# DRV8313_Main.net
KiCad netlist of a schematic drawn in Altium Designer
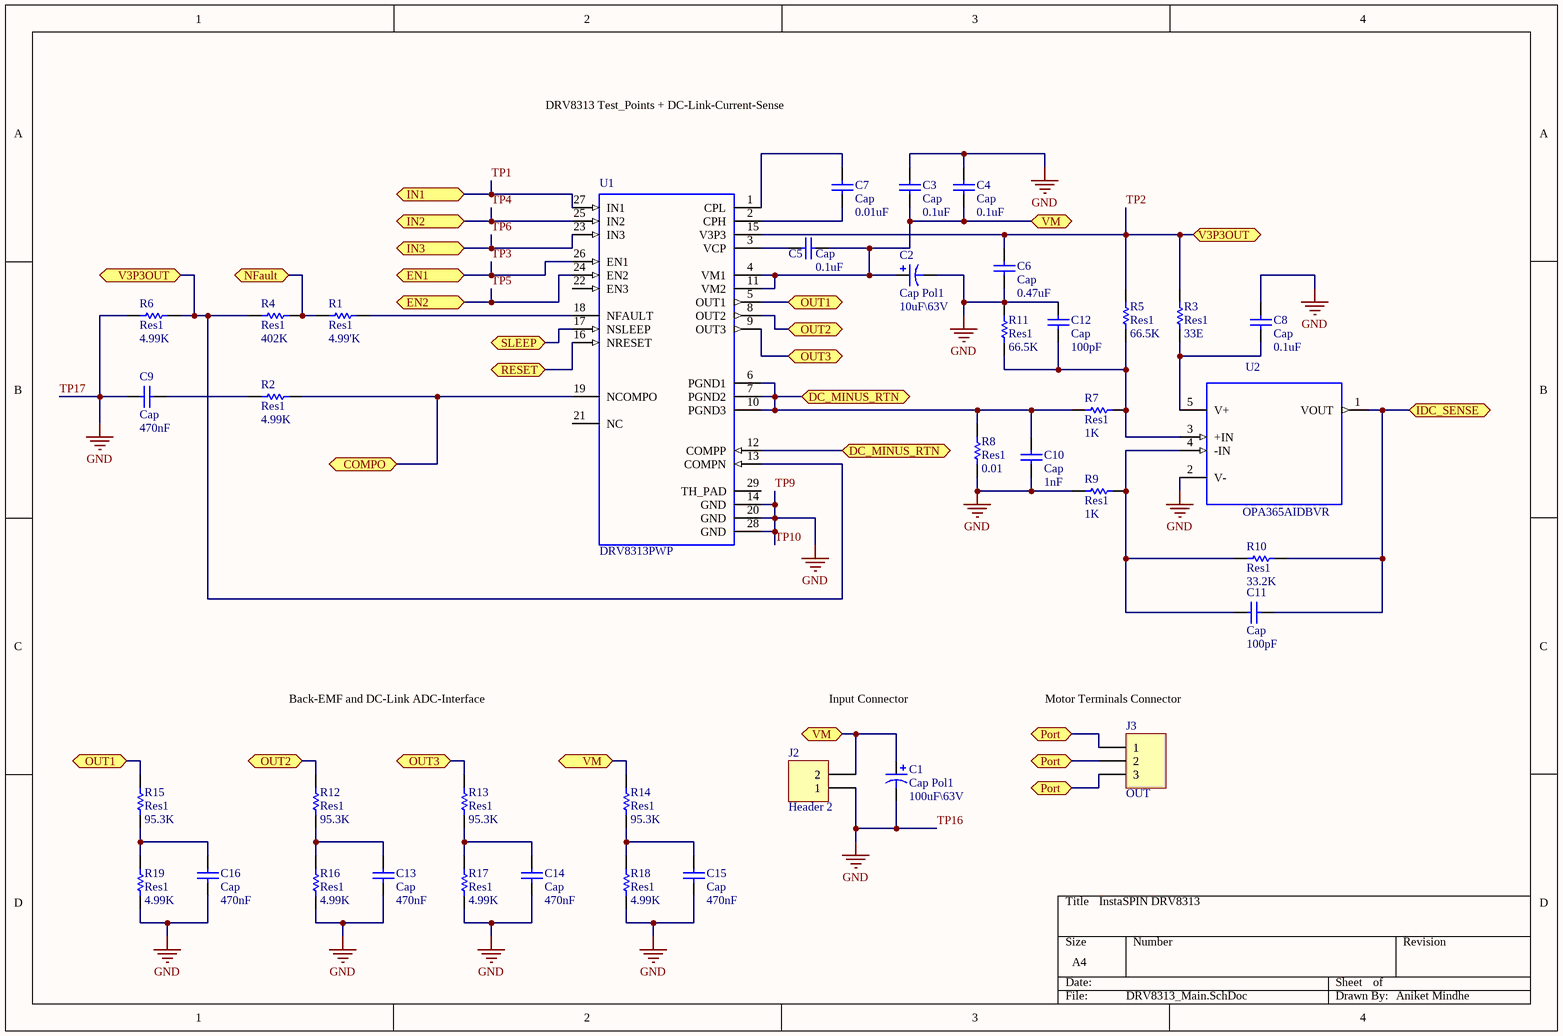
[diagram p0: DRV8313_Main.SchDoc]

(export (version "E")
  (design (tool "Eeschema 10.0.6"))
  (components
    (comp (ref "C1")
      (value "Cap Pol1")
      (footprint "RB7.6-15")
      (description "Polarized Capacitor (Radial)")
      (fields (field (name "ALTIUM_VALUE") "100u~{F}63V") (field (name "PUBLISHER") "Altium Limited"))
      (libsource (lib "Miscellaneous Devices") (part "Cap Pol1"))
    )
    (comp (ref "C2")
      (value "Cap Pol1")
      (footprint "RB7.6-15")
      (description "Polarized Capacitor (Radial)")
      (fields (field (name "ALTIUM_VALUE") "10u~{F}63V") (field (name "PUBLISHER") "Altium Limited"))
      (libsource (lib "Miscellaneous Devices") (part "Cap Pol1"))
    )
    (comp (ref "C3")
      (value "Cap")
      (footprint "RAD-0.3")
      (description "Capacitor")
      (fields (field (name "ALTIUM_VALUE") "0.1uF") (field (name "PUBLISHER") "Altium Limited"))
      (libsource (lib "Miscellaneous Devices") (part "Cap"))
    )
    (comp (ref "C4")
      (value "Cap")
      (footprint "RAD-0.3")
      (description "Capacitor")
      (fields (field (name "ALTIUM_VALUE") "0.1uF") (field (name "PUBLISHER") "Altium Limited"))
      (libsource (lib "Miscellaneous Devices") (part "Cap"))
    )
    (comp (ref "C5")
      (value "Cap")
      (footprint "RAD-0.3")
      (description "Capacitor")
      (fields (field (name "ALTIUM_VALUE") "0.1uF") (field (name "PUBLISHER") "Altium Limited"))
      (libsource (lib "Miscellaneous Devices") (part "Cap"))
    )
    (comp (ref "C6")
      (value "Cap")
      (footprint "RAD-0.3")
      (description "Capacitor")
      (fields (field (name "ALTIUM_VALUE") "0.47uF") (field (name "PUBLISHER") "Altium Limited"))
      (libsource (lib "Miscellaneous Devices") (part "Cap"))
    )
    (comp (ref "C7")
      (value "Cap")
      (footprint "RAD-0.3")
      (description "Capacitor")
      (fields (field (name "ALTIUM_VALUE") "0.01uF") (field (name "PUBLISHER") "Altium Limited"))
      (libsource (lib "Miscellaneous Devices") (part "Cap"))
    )
    (comp (ref "C8")
      (value "Cap")
      (footprint "RAD-0.3")
      (description "Capacitor")
      (fields (field (name "ALTIUM_VALUE") "0.1uF") (field (name "PUBLISHER") "Altium Limited"))
      (libsource (lib "Miscellaneous Devices") (part "Cap"))
    )
    (comp (ref "C9")
      (value "Cap")
      (footprint "RAD-0.3")
      (description "Capacitor")
      (fields (field (name "ALTIUM_VALUE") "470nF") (field (name "PUBLISHER") "Altium Limited"))
      (libsource (lib "Miscellaneous Devices") (part "Cap"))
    )
    (comp (ref "C10")
      (value "Cap")
      (footprint "RAD-0.3")
      (description "Capacitor")
      (fields (field (name "ALTIUM_VALUE") "1nF") (field (name "PUBLISHER") "Altium Limited"))
      (libsource (lib "Miscellaneous Devices") (part "Cap"))
    )
    (comp (ref "C11")
      (value "Cap")
      (footprint "RAD-0.3")
      (description "Capacitor")
      (fields (field (name "ALTIUM_VALUE") "100pF") (field (name "PUBLISHER") "Altium Limited"))
      (libsource (lib "Miscellaneous Devices") (part "Cap"))
    )
    (comp (ref "C12")
      (value "Cap")
      (footprint "RAD-0.3")
      (description "Capacitor")
      (fields (field (name "ALTIUM_VALUE") "100pF") (field (name "PUBLISHER") "Altium Limited"))
      (libsource (lib "Miscellaneous Devices") (part "Cap"))
    )
    (comp (ref "C13")
      (value "Cap")
      (footprint "RAD-0.3")
      (description "Capacitor")
      (fields (field (name "ALTIUM_VALUE") "470nF") (field (name "PUBLISHER") "Altium Limited"))
      (libsource (lib "Miscellaneous Devices") (part "Cap"))
    )
    (comp (ref "C14")
      (value "Cap")
      (footprint "RAD-0.3")
      (description "Capacitor")
      (fields (field (name "ALTIUM_VALUE") "470nF") (field (name "PUBLISHER") "Altium Limited"))
      (libsource (lib "Miscellaneous Devices") (part "Cap"))
    )
    (comp (ref "C15")
      (value "Cap")
      (footprint "RAD-0.3")
      (description "Capacitor")
      (fields (field (name "ALTIUM_VALUE") "470nF") (field (name "PUBLISHER") "Altium Limited"))
      (libsource (lib "Miscellaneous Devices") (part "Cap"))
    )
    (comp (ref "C16")
      (value "Cap")
      (footprint "RAD-0.3")
      (description "Capacitor")
      (fields (field (name "ALTIUM_VALUE") "470nF") (field (name "PUBLISHER") "Altium Limited"))
      (libsource (lib "Miscellaneous Devices") (part "Cap"))
    )
    (comp (ref "J2")
      (value "Header 2")
      (footprint "HDR1X2")
      (description "Header, 2-Pin")
      (fields (field (name "PUBLISHER") "Altium Limited"))
      (libsource (lib "Miscellaneous Connectors") (part "Header 2"))
    )
    (comp (ref "J3")
      (value "OUT")
      (footprint "HDR1X3")
      (description "Header, 3-Pin")
      (fields (field (name "PUBLISHER") "Altium Limited"))
      (libsource (lib "Miscellaneous Connectors") (part "Header 3"))
    )
    (comp (ref "R1")
      (value "Res1")
      (footprint "AXIAL-0.3")
      (description "Resistor")
      (fields (field (name "ALTIUM_VALUE") "4.99'K") (field (name "PUBLISHER") "Altium Limited"))
      (libsource (lib "Miscellaneous Devices") (part "Res1"))
    )
    (comp (ref "R2")
      (value "Res1")
      (footprint "AXIAL-0.3")
      (description "Resistor")
      (fields (field (name "ALTIUM_VALUE") "4.99K") (field (name "PUBLISHER") "Altium Limited"))
      (libsource (lib "Miscellaneous Devices") (part "Res1"))
    )
    (comp (ref "R3")
      (value "Res1")
      (footprint "AXIAL-0.3")
      (description "Resistor")
      (fields (field (name "ALTIUM_VALUE") "33E") (field (name "PUBLISHER") "Altium Limited"))
      (libsource (lib "Miscellaneous Devices") (part "Res1"))
    )
    (comp (ref "R4")
      (value "Res1")
      (footprint "AXIAL-0.3")
      (description "Resistor")
      (fields (field (name "ALTIUM_VALUE") "402K") (field (name "PUBLISHER") "Altium Limited"))
      (libsource (lib "Miscellaneous Devices") (part "Res1"))
    )
    (comp (ref "R5")
      (value "Res1")
      (footprint "AXIAL-0.3")
      (description "Resistor")
      (fields (field (name "ALTIUM_VALUE") "66.5K") (field (name "PUBLISHER") "Altium Limited"))
      (libsource (lib "Miscellaneous Devices") (part "Res1"))
    )
    (comp (ref "R6")
      (value "Res1")
      (footprint "AXIAL-0.3")
      (description "Resistor")
      (fields (field (name "ALTIUM_VALUE") "4.99K") (field (name "PUBLISHER") "Altium Limited"))
      (libsource (lib "Miscellaneous Devices") (part "Res1"))
    )
    (comp (ref "R7")
      (value "Res1")
      (footprint "AXIAL-0.3")
      (description "Resistor")
      (fields (field (name "ALTIUM_VALUE") "1K") (field (name "PUBLISHER") "Altium Limited"))
      (libsource (lib "Miscellaneous Devices") (part "Res1"))
    )
    (comp (ref "R8")
      (value "Res1")
      (footprint "AXIAL-0.3")
      (description "Resistor")
      (fields (field (name "ALTIUM_VALUE") "0.01") (field (name "PUBLISHER") "Altium Limited"))
      (libsource (lib "Miscellaneous Devices") (part "Res1"))
    )
    (comp (ref "R9")
      (value "Res1")
      (footprint "AXIAL-0.3")
      (description "Resistor")
      (fields (field (name "ALTIUM_VALUE") "1K") (field (name "PUBLISHER") "Altium Limited"))
      (libsource (lib "Miscellaneous Devices") (part "Res1"))
    )
    (comp (ref "R10")
      (value "Res1")
      (footprint "AXIAL-0.3")
      (description "Resistor")
      (fields (field (name "ALTIUM_VALUE") "33.2K") (field (name "PUBLISHER") "Altium Limited"))
      (libsource (lib "Miscellaneous Devices") (part "Res1"))
    )
    (comp (ref "R11")
      (value "Res1")
      (footprint "AXIAL-0.3")
      (description "Resistor")
      (fields (field (name "ALTIUM_VALUE") "66.5K") (field (name "PUBLISHER") "Altium Limited"))
      (libsource (lib "Miscellaneous Devices") (part "Res1"))
    )
    (comp (ref "R12")
      (value "Res1")
      (footprint "AXIAL-0.3")
      (description "Resistor")
      (fields (field (name "ALTIUM_VALUE") "95.3K") (field (name "PUBLISHER") "Altium Limited"))
      (libsource (lib "Miscellaneous Devices") (part "Res1"))
    )
    (comp (ref "R13")
      (value "Res1")
      (footprint "AXIAL-0.3")
      (description "Resistor")
      (fields (field (name "ALTIUM_VALUE") "95.3K") (field (name "PUBLISHER") "Altium Limited"))
      (libsource (lib "Miscellaneous Devices") (part "Res1"))
    )
    (comp (ref "R14")
      (value "Res1")
      (footprint "AXIAL-0.3")
      (description "Resistor")
      (fields (field (name "ALTIUM_VALUE") "95.3K") (field (name "PUBLISHER") "Altium Limited"))
      (libsource (lib "Miscellaneous Devices") (part "Res1"))
    )
    (comp (ref "R15")
      (value "Res1")
      (footprint "AXIAL-0.3")
      (description "Resistor")
      (fields (field (name "ALTIUM_VALUE") "95.3K") (field (name "PUBLISHER") "Altium Limited"))
      (libsource (lib "Miscellaneous Devices") (part "Res1"))
    )
    (comp (ref "R16")
      (value "Res1")
      (footprint "AXIAL-0.3")
      (description "Resistor")
      (fields (field (name "ALTIUM_VALUE") "4.99K") (field (name "PUBLISHER") "Altium Limited"))
      (libsource (lib "Miscellaneous Devices") (part "Res1"))
    )
    (comp (ref "R17")
      (value "Res1")
      (footprint "AXIAL-0.3")
      (description "Resistor")
      (fields (field (name "ALTIUM_VALUE") "4.99K") (field (name "PUBLISHER") "Altium Limited"))
      (libsource (lib "Miscellaneous Devices") (part "Res1"))
    )
    (comp (ref "R18")
      (value "Res1")
      (footprint "AXIAL-0.3")
      (description "Resistor")
      (fields (field (name "ALTIUM_VALUE") "4.99K") (field (name "PUBLISHER") "Altium Limited"))
      (libsource (lib "Miscellaneous Devices") (part "Res1"))
    )
    (comp (ref "R19")
      (value "Res1")
      (footprint "AXIAL-0.3")
      (description "Resistor")
      (fields (field (name "ALTIUM_VALUE") "4.99K") (field (name "PUBLISHER") "Altium Limited"))
      (libsource (lib "Miscellaneous Devices") (part "Res1"))
    )
    (comp (ref "U1")
      (value "DRV8313PWP")
      (footprint "SOP28P65_970X640X120L60X24T483X275N")
      (description "2.5A Three Phase Brushless DC Motor Driver _PWM Ctrl_ 28-HTSSOP -40 to 85")
      (fields (field (name "MF") "Texas Instruments"))
      (libsource (lib "DRV8313PWP") (part "DRV8313PWP"))
    )
    (comp (ref "U2")
      (value "OPA365AIDBVR")
      (footprint "SOT95P280X145-5N")
      (description "2.2V, 50MHz, Low-Noise, Single-Supply Rail-to-Rail Operational Amplifier 5-SOT-23 -40 to 125")
      (fields (field (name "MF") "Texas Instruments"))
      (libsource (lib "OPA365AIDBVR") (part "OPA365AIDBVR"))
    )
  )
  (nets
    (net (code "1") (name "/COMPO") (class "Default")
      (node (ref "R2") (pin "2") (pinfunction "2_2") (pintype "passive"))
      (node (ref "U1") (pin "19") (pinfunction "NCOMPO_19") (pintype "open_collector"))
    )
    (net (code "2") (name "/DC_MINUS_RTN") (class "Default")
      (node (ref "C10") (pin "2") (pinfunction "2_2") (pintype "passive"))
      (node (ref "R7") (pin "1") (pinfunction "1_1") (pintype "passive"))
      (node (ref "R8") (pin "2") (pinfunction "2_2") (pintype "passive"))
      (node (ref "U1") (pin "10") (pinfunction "PGND3_10") (pintype "power_in"))
      (node (ref "U1") (pin "12") (pinfunction "COMPP_12") (pintype "input"))
      (node (ref "U1") (pin "6") (pinfunction "PGND1_6") (pintype "power_in"))
      (node (ref "U1") (pin "7") (pinfunction "PGND2_7") (pintype "power_in"))
    )
    (net (code "3") (name "/IDC_SENSE") (class "Default")
      (node (ref "C11") (pin "2") (pinfunction "2_2") (pintype "passive"))
      (node (ref "R10") (pin "1") (pinfunction "1_1") (pintype "passive"))
      (node (ref "U2") (pin "1") (pinfunction "VOUT_1") (pintype "output"))
    )
    (net (code "4") (name "/NFault") (class "Default")
      (node (ref "R1") (pin "1") (pinfunction "1_1") (pintype "passive"))
      (node (ref "R4") (pin "2") (pinfunction "2_2") (pintype "passive"))
    )
    (net (code "5") (name "/OUT1") (class "Default")
      (node (ref "R15") (pin "2") (pinfunction "2_2") (pintype "passive"))
      (node (ref "U1") (pin "5") (pinfunction "OUT1_5") (pintype "output"))
    )
    (net (code "6") (name "/OUT2") (class "Default")
      (node (ref "R12") (pin "2") (pinfunction "2_2") (pintype "passive"))
      (node (ref "U1") (pin "8") (pinfunction "OUT2_8") (pintype "output"))
    )
    (net (code "7") (name "/OUT3") (class "Default")
      (node (ref "R13") (pin "2") (pinfunction "2_2") (pintype "passive"))
      (node (ref "U1") (pin "9") (pinfunction "OUT3_9") (pintype "output"))
    )
    (net (code "8") (name "/Port") (class "Default")
      (node (ref "J3") (pin "1") (pinfunction "1_1") (pintype "passive"))
      (node (ref "J3") (pin "2") (pinfunction "2_2") (pintype "passive"))
      (node (ref "J3") (pin "3") (pinfunction "3_3") (pintype "passive"))
    )
    (net (code "9") (name "/RESET") (class "Default")
      (node (ref "U1") (pin "16") (pinfunction "NRESET_16") (pintype "input"))
    )
    (net (code "10") (name "/SLEEP") (class "Default")
      (node (ref "U1") (pin "17") (pinfunction "NSLEEP_17") (pintype "input"))
    )
    (net (code "11") (name "/TP1") (class "Default")
      (node (ref "U1") (pin "27") (pinfunction "IN1_27") (pintype "input"))
    )
    (net (code "12") (name "/TP2") (class "Default")
      (node (ref "C6") (pin "2") (pinfunction "2_2") (pintype "passive"))
      (node (ref "R3") (pin "2") (pinfunction "2_2") (pintype "passive"))
      (node (ref "R4") (pin "1") (pinfunction "1_1") (pintype "passive"))
      (node (ref "R5") (pin "2") (pinfunction "2_2") (pintype "passive"))
      (node (ref "R6") (pin "1") (pinfunction "1_1") (pintype "passive"))
      (node (ref "U1") (pin "13") (pinfunction "COMPN_13") (pintype "input"))
      (node (ref "U1") (pin "15") (pinfunction "V3P3_15") (pintype "power_in"))
    )
    (net (code "13") (name "/TP3") (class "Default")
      (node (ref "U1") (pin "26") (pinfunction "EN1_26") (pintype "input"))
    )
    (net (code "14") (name "/TP4") (class "Default")
      (node (ref "U1") (pin "25") (pinfunction "IN2_25") (pintype "input"))
    )
    (net (code "15") (name "/TP5") (class "Default")
      (node (ref "U1") (pin "24") (pinfunction "EN2_24") (pintype "input"))
    )
    (net (code "16") (name "/TP6") (class "Default")
      (node (ref "U1") (pin "23") (pinfunction "IN3_23") (pintype "input"))
    )
    (net (code "17") (name "/VM") (class "Default")
      (node (ref "C1") (pin "1") (pinfunction "1_1") (pintype "passive"))
      (node (ref "C2") (pin "1") (pinfunction "1_1") (pintype "passive"))
      (node (ref "C3") (pin "1") (pinfunction "1_1") (pintype "passive"))
      (node (ref "C4") (pin "1") (pinfunction "1_1") (pintype "passive"))
      (node (ref "C5") (pin "1") (pinfunction "1_1") (pintype "passive"))
      (node (ref "J2") (pin "2") (pinfunction "2_2") (pintype "passive"))
      (node (ref "R14") (pin "2") (pinfunction "2_2") (pintype "passive"))
      (node (ref "U1") (pin "11") (pinfunction "VM2_11") (pintype "power_in"))
      (node (ref "U1") (pin "4") (pinfunction "VM1_4") (pintype "power_in"))
    )
    (net (code "18") (name "GND") (class "Default")
      (node (ref "C1") (pin "2") (pinfunction "2_2") (pintype "passive"))
      (node (ref "C10") (pin "1") (pinfunction "1_1") (pintype "passive"))
      (node (ref "C12") (pin "2") (pinfunction "2_2") (pintype "passive"))
      (node (ref "C13") (pin "1") (pinfunction "1_1") (pintype "passive"))
      (node (ref "C14") (pin "1") (pinfunction "1_1") (pintype "passive"))
      (node (ref "C15") (pin "1") (pinfunction "1_1") (pintype "passive"))
      (node (ref "C16") (pin "1") (pinfunction "1_1") (pintype "passive"))
      (node (ref "C2") (pin "2") (pinfunction "2_2") (pintype "passive"))
      (node (ref "C3") (pin "2") (pinfunction "2_2") (pintype "passive"))
      (node (ref "C4") (pin "2") (pinfunction "2_2") (pintype "passive"))
      (node (ref "C6") (pin "1") (pinfunction "1_1") (pintype "passive"))
      (node (ref "C8") (pin "2") (pinfunction "2_2") (pintype "passive"))
      (node (ref "C9") (pin "1") (pinfunction "1_1") (pintype "passive"))
      (node (ref "J2") (pin "1") (pinfunction "1_1") (pintype "passive"))
      (node (ref "R11") (pin "2") (pinfunction "2_2") (pintype "passive"))
      (node (ref "R16") (pin "1") (pinfunction "1_1") (pintype "passive"))
      (node (ref "R17") (pin "1") (pinfunction "1_1") (pintype "passive"))
      (node (ref "R18") (pin "1") (pinfunction "1_1") (pintype "passive"))
      (node (ref "R19") (pin "1") (pinfunction "1_1") (pintype "passive"))
      (node (ref "R6") (pin "2") (pinfunction "2_2") (pintype "passive"))
      (node (ref "R8") (pin "1") (pinfunction "1_1") (pintype "passive"))
      (node (ref "R9") (pin "1") (pinfunction "1_1") (pintype "passive"))
      (node (ref "U1") (pin "14") (pinfunction "GND_14") (pintype "power_in"))
      (node (ref "U1") (pin "20") (pinfunction "GND_20") (pintype "power_in"))
      (node (ref "U1") (pin "28") (pinfunction "GND_28") (pintype "power_in"))
      (node (ref "U2") (pin "2") (pinfunction "V-_2") (pintype "power_in"))
    )
    (net (code "19") (name "Net-(C9-Pad2)") (class "Default")
      (node (ref "C9") (pin "2") (pinfunction "2_2") (pintype "passive"))
      (node (ref "R2") (pin "1") (pinfunction "1_1") (pintype "passive"))
    )
    (net (code "20") (name "Net-(C13-Pad2)") (class "Default")
      (node (ref "C13") (pin "2") (pinfunction "2_2") (pintype "passive"))
      (node (ref "R12") (pin "1") (pinfunction "1_1") (pintype "passive"))
      (node (ref "R16") (pin "2") (pinfunction "2_2") (pintype "passive"))
    )
    (net (code "21") (name "Net-(C14-Pad2)") (class "Default")
      (node (ref "C14") (pin "2") (pinfunction "2_2") (pintype "passive"))
      (node (ref "R13") (pin "1") (pinfunction "1_1") (pintype "passive"))
      (node (ref "R17") (pin "2") (pinfunction "2_2") (pintype "passive"))
    )
    (net (code "22") (name "Net-(C15-Pad2)") (class "Default")
      (node (ref "C15") (pin "2") (pinfunction "2_2") (pintype "passive"))
      (node (ref "R14") (pin "1") (pinfunction "1_1") (pintype "passive"))
      (node (ref "R18") (pin "2") (pinfunction "2_2") (pintype "passive"))
    )
    (net (code "23") (name "Net-(C16-Pad2)") (class "Default")
      (node (ref "C16") (pin "2") (pinfunction "2_2") (pintype "passive"))
      (node (ref "R15") (pin "1") (pinfunction "1_1") (pintype "passive"))
      (node (ref "R19") (pin "2") (pinfunction "2_2") (pintype "passive"))
    )
    (net (code "24") (name "Net-(U1-CPH)") (class "Default")
      (node (ref "C7") (pin "1") (pinfunction "1_1") (pintype "passive"))
      (node (ref "U1") (pin "2") (pinfunction "CPH_2") (pintype "power_in"))
    )
    (net (code "25") (name "Net-(U1-CPL)") (class "Default")
      (node (ref "C7") (pin "2") (pinfunction "2_2") (pintype "passive"))
      (node (ref "U1") (pin "1") (pinfunction "CPL_1") (pintype "power_in"))
    )
    (net (code "26") (name "Net-(U1-NFAULT)") (class "Default")
      (node (ref "R1") (pin "2") (pinfunction "2_2") (pintype "passive"))
      (node (ref "U1") (pin "18") (pinfunction "NFAULT_18") (pintype "open_collector"))
    )
    (net (code "27") (name "Net-(U1-VCP)") (class "Default")
      (node (ref "C5") (pin "2") (pinfunction "2_2") (pintype "passive"))
      (node (ref "U1") (pin "3") (pinfunction "VCP_3") (pintype "power_in"))
    )
    (net (code "28") (name "Net-(U2-+IN)") (class "Default")
      (node (ref "C12") (pin "1") (pinfunction "1_1") (pintype "passive"))
      (node (ref "R11") (pin "1") (pinfunction "1_1") (pintype "passive"))
      (node (ref "R5") (pin "1") (pinfunction "1_1") (pintype "passive"))
      (node (ref "R7") (pin "2") (pinfunction "2_2") (pintype "passive"))
      (node (ref "U2") (pin "3") (pinfunction "+IN_3") (pintype "input"))
    )
    (net (code "29") (name "Net-(U2--IN)") (class "Default")
      (node (ref "C11") (pin "1") (pinfunction "1_1") (pintype "passive"))
      (node (ref "R10") (pin "2") (pinfunction "2_2") (pintype "passive"))
      (node (ref "R9") (pin "2") (pinfunction "2_2") (pintype "passive"))
      (node (ref "U2") (pin "4") (pinfunction "-IN_4") (pintype "input"))
    )
    (net (code "30") (name "Net-(U2-V+)") (class "Default")
      (node (ref "C8") (pin "1") (pinfunction "1_1") (pintype "passive"))
      (node (ref "R3") (pin "1") (pinfunction "1_1") (pintype "passive"))
      (node (ref "U2") (pin "5") (pinfunction "V+_5") (pintype "power_in"))
    )
    (net (code "31") (name "unconnected-(U1-EN3-Pad22)") (class "Default")
      (node (ref "U1") (pin "22") (pinfunction "EN3_22") (pintype "input"))
    )
    (net (code "32") (name "unconnected-(U1-NC-Pad21)") (class "Default")
      (node (ref "U1") (pin "21") (pinfunction "NC_21") (pintype "passive"))
    )
    (net (code "33") (name "unconnected-(U1-TH_PAD-Pad29)") (class "Default")
      (node (ref "U1") (pin "29") (pinfunction "TH_PAD_29") (pintype "power_in"))
    )
  )
)
